# Power_CH341T.net
KiCad netlist of a schematic drawn in Altium Designer
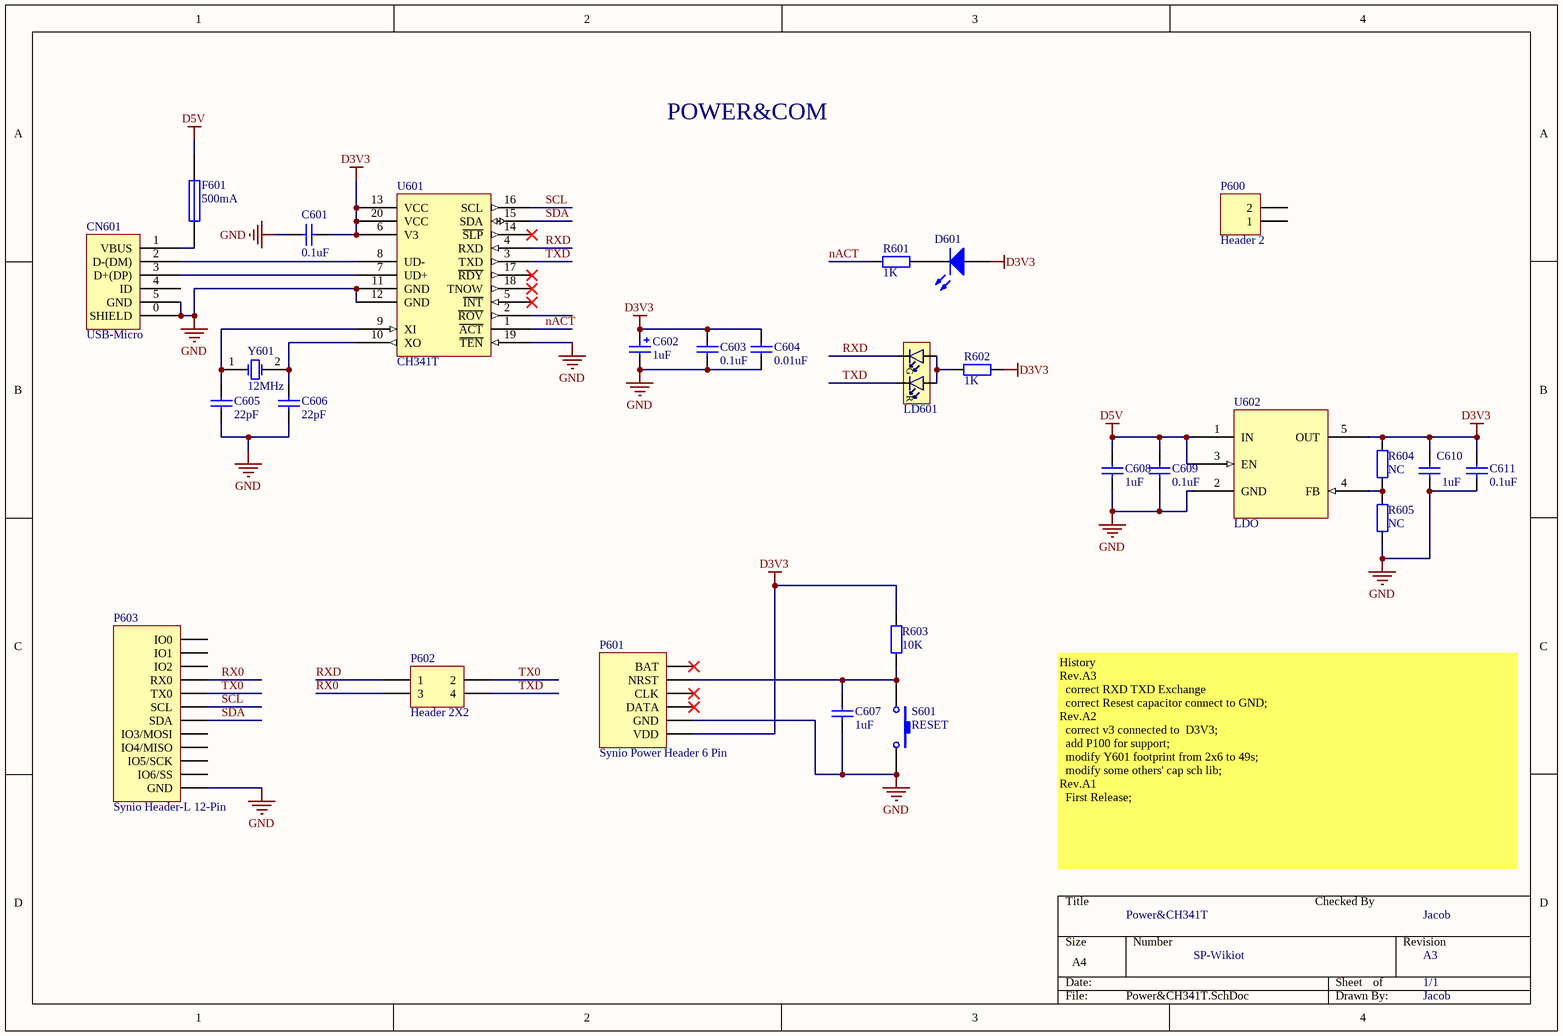
[diagram p0: Power&CH341T.SchDoc]

(export (version "E")
  (design (tool "Eeschema 10.0.6"))
  (components
    (comp (ref "C601")
      (value "0.1uF")
      (footprint "C0603L")
      (description "Capacitor")
      (libsource (lib "Studio") (part "Cap"))
    )
    (comp (ref "C602")
      (value "1uF")
      (footprint "0805M")
      (description "Polarized Capacitor (Radial)")
      (fields (field (name "PUBLISHER") "Altium Limited"))
      (libsource (lib "Studio") (part "Cap Pol1"))
    )
    (comp (ref "C603")
      (value "0.1uF")
      (footprint "C0603L")
      (description "Capacitor")
      (fields (field (name "Comment") "Cap") (field (name "PUBLISHER") "Altium Limited"))
      (libsource (lib "Miscellaneous Devices") (part "Cap"))
    )
    (comp (ref "C604")
      (value "0.01uF")
      (footprint "C0603L")
      (description "Capacitor")
      (fields (field (name "Comment") "Cap") (field (name "PUBLISHER") "Altium Limited"))
      (libsource (lib "Miscellaneous Devices") (part "Cap"))
    )
    (comp (ref "C605")
      (value "22pF")
      (footprint "C0603L")
      (description "Capacitor")
      (fields (field (name "Comment") "Cap") (field (name "PUBLISHER") "Altium Limited"))
      (libsource (lib "Miscellaneous Devices") (part "Cap"))
    )
    (comp (ref "C606")
      (value "22pF")
      (footprint "C0603L")
      (description "Capacitor")
      (fields (field (name "Comment") "Cap") (field (name "PUBLISHER") "Altium Limited"))
      (libsource (lib "Miscellaneous Devices") (part "Cap"))
    )
    (comp (ref "C607")
      (value "1uF")
      (footprint "C0603L")
      (description "Capacitor")
      (fields (field (name "PUBLISHER") "Altium Limited"))
      (libsource (lib "Miscellaneous Devices") (part "Cap"))
    )
    (comp (ref "C608")
      (value "1uF")
      (footprint "C0603L")
      (description "Capacitor")
      (fields (field (name "Comment") "Cap") (field (name "PUBLISHER") "Altium Limited"))
      (libsource (lib "Miscellaneous Devices") (part "Cap"))
    )
    (comp (ref "C609")
      (value "0.1uF")
      (footprint "C0603L")
      (description "Capacitor")
      (fields (field (name "Comment") "Cap") (field (name "PUBLISHER") "Altium Limited"))
      (libsource (lib "Miscellaneous Devices") (part "Cap"))
    )
    (comp (ref "C610")
      (value "1uF")
      (footprint "C0603L")
      (description "Capacitor")
      (fields (field (name "Comment") "Cap") (field (name "PUBLISHER") "Altium Limited"))
      (libsource (lib "Miscellaneous Devices") (part "Cap"))
    )
    (comp (ref "C611")
      (value "0.1uF")
      (footprint "C0603L")
      (description "Capacitor")
      (fields (field (name "Comment") "Cap") (field (name "PUBLISHER") "Altium Limited"))
      (libsource (lib "Miscellaneous Devices") (part "Cap"))
    )
    (comp (ref "CN601")
      (value "USB-Micro")
      (footprint "USB-MICRO-Lite")
      (libsource (lib "Connector") (part "USB-Micro"))
    )
    (comp (ref "D601")
      (value "LED1")
      (footprint "0603pn")
      (description "Typical RED GaAs LED")
      (fields (field (name "PUBLISHER") "Altium Limited"))
      (libsource (lib "Studio") (part "LED1"))
    )
    (comp (ref "F601")
      (value "500mA")
      (footprint "0805")
      (description "Fuse")
      (fields (field (name "PUBLISHER") "Altium Limited"))
      (libsource (lib "Studio") (part "Fuse 1"))
    )
    (comp (ref "LD601")
      (value "LTST-C195KGJRKT")
      (footprint "0805-LED-Bi")
      (description "Avago, HSMF-A203 Bi-Color LED")
      (fields
        (field (name "MANUFACTURER") "Lite-On Inc")
        (field (name "2ND SOURCE PART NUMBER") "859-LTST-C195KGJRKT")
        (field (name "PUBLISHER") "Nordic Semiconductor")
      )
      (libsource (lib "Misc") (part "LED-DUAL"))
    )
    (comp (ref "P600")
      (value "Header 2")
      (footprint "HDR1X2")
      (description "Header, 2-Pin")
      (fields (field (name "PUBLISHER") "Altium Limited"))
      (libsource (lib "Miscellaneous Connectors") (part "Header 2"))
    )
    (comp (ref "P601")
      (value "Synio Power Header 6 Pin")
      (footprint "HDR1X6/2.54MM")
      (libsource (lib "Connector") (part "Synio Power Header 6 Pin"))
    )
    (comp (ref "P602")
      (value "Header 2X2")
      (footprint "HDR2X2/2.54MM")
      (description "Header, 2-Pin, Dual row")
      (fields (field (name "PUBLISHER") "Altium Limited"))
      (libsource (lib "Miscellaneous Connectors") (part "Header 2X2"))
    )
    (comp (ref "P603")
      (value "Synio Header-L 12-Pin")
      (footprint "HDR1X12")
      (description "Synio Header-L, 12-Pin")
      (fields (field (name "PUBLISHER") "Altium Limited"))
      (libsource (lib "Connector") (part "Synio Header-L 12-Pin"))
    )
    (comp (ref "R601")
      (value "1K")
      (footprint "R0603")
      (description "Resistor")
      (fields (field (name "PUBLISHER") "Altium Limited"))
      (libsource (lib "Studio") (part "Res"))
    )
    (comp (ref "R602")
      (value "1K")
      (footprint "0603M")
      (description "Resistor")
      (fields (field (name "PUBLISHER") "Altium Limited"))
      (libsource (lib "") (part "Res2_2"))
    )
    (comp (ref "R603")
      (value "10K")
      (footprint "0603M")
      (description "Resistor")
      (fields (field (name "PUBLISHER") "Altium Limited"))
      (libsource (lib "") (part "Res2_1"))
    )
    (comp (ref "R604")
      (value "NC")
      (footprint "0603M")
      (description "Resistor")
      (fields (field (name "PUBLISHER") "Altium Limited"))
      (libsource (lib "") (part "Res2_1"))
    )
    (comp (ref "R605")
      (value "NC")
      (footprint "0603M")
      (description "Resistor")
      (fields (field (name "PUBLISHER") "Altium Limited"))
      (libsource (lib "Miscellaneous Devices") (part "Res2"))
    )
    (comp (ref "S601")
      (value "RESET")
      (footprint "KEY-2x4-SMD")
      (description "Switch")
      (fields (field (name "PUBLISHER") "Altium Limited"))
      (libsource (lib "Miscellaneous Devices") (part "SW-PB"))
    )
    (comp (ref "U601") (value "CH341T") (footprint "SSOP20") (libsource (lib "Studio") (part "CH341T")))
    (comp (ref "U602")
      (value "LDO")
      (footprint "SOT23-5")
      (description "General LDO SOT23-5")
      (libsource (lib "Power") (part "LDO-SOT23-5"))
    )
    (comp (ref "Y601")
      (value "12MHz")
      (footprint "XTAL_49S")
      (description "Crystal Oscillator")
      (fields (field (name "PUBLISHER") "Altium Limited"))
      (libsource (lib "Miscellaneous Devices") (part "XTAL"))
    )
  )
  (nets
    (net (code "1") (name "/RX0") (class "Default")
      (node (ref "P602") (pin "3") (pinfunction "3_3") (pintype "passive"))
      (node (ref "P603") (pin "9") (pinfunction "RX0_9") (pintype "passive"))
    )
    (net (code "2") (name "/RXD") (class "Default")
      (node (ref "LD601") (pin "1") (pinfunction "C1_1") (pintype "passive"))
      (node (ref "P602") (pin "1") (pinfunction "1_1") (pintype "passive"))
      (node (ref "U601") (pin "4") (pinfunction "RXD_4") (pintype "input"))
    )
    (net (code "3") (name "/SCL") (class "Default")
      (node (ref "P603") (pin "7") (pinfunction "SCL_7") (pintype "passive"))
      (node (ref "U601") (pin "16") (pinfunction "SCL_16") (pintype "output"))
    )
    (net (code "4") (name "/SDA") (class "Default")
      (node (ref "P603") (pin "6") (pinfunction "SDA_6") (pintype "passive"))
      (node (ref "U601") (pin "15") (pinfunction "SDA_15") (pintype "bidirectional"))
    )
    (net (code "5") (name "/TX0") (class "Default")
      (node (ref "P602") (pin "2") (pinfunction "2_2") (pintype "passive"))
      (node (ref "P603") (pin "8") (pinfunction "TX0_8") (pintype "passive"))
    )
    (net (code "6") (name "/TXD") (class "Default")
      (node (ref "LD601") (pin "2") (pinfunction "C2_2") (pintype "passive"))
      (node (ref "P602") (pin "4") (pinfunction "4_4") (pintype "passive"))
      (node (ref "U601") (pin "3") (pinfunction "TXD_3") (pintype "output"))
    )
    (net (code "7") (name "/nACT") (class "Default")
      (node (ref "R601") (pin "1") (pinfunction "1_1") (pintype "passive"))
      (node (ref "U601") (pin "1") (pinfunction "~{ACT}_1") (pintype "power_in"))
    )
    (net (code "8") (name "D3V3") (class "Default")
      (node (ref "C601") (pin "2") (pinfunction "2_2") (pintype "passive"))
      (node (ref "C602") (pin "1") (pinfunction "1_1") (pintype "passive"))
      (node (ref "C603") (pin "2") (pinfunction "2_2") (pintype "passive"))
      (node (ref "C604") (pin "2") (pinfunction "2_2") (pintype "passive"))
      (node (ref "C610") (pin "2") (pinfunction "2_2") (pintype "passive"))
      (node (ref "C611") (pin "2") (pinfunction "2_2") (pintype "passive"))
      (node (ref "D601") (pin "1") (pinfunction "A_1") (pintype "passive"))
      (node (ref "P601") (pin "1") (pinfunction "VDD_1") (pintype "passive"))
      (node (ref "R602") (pin "1") (pinfunction "1_1") (pintype "passive"))
      (node (ref "R603") (pin "1") (pinfunction "1_1") (pintype "passive"))
      (node (ref "R604") (pin "1") (pinfunction "1_1") (pintype "passive"))
      (node (ref "U601") (pin "13") (pinfunction "VCC_13") (pintype "passive"))
      (node (ref "U601") (pin "20") (pinfunction "VCC_20") (pintype "passive"))
      (node (ref "U601") (pin "6") (pinfunction "V3_6") (pintype "power_in"))
      (node (ref "U602") (pin "5") (pinfunction "OUT_5") (pintype "power_in"))
    )
    (net (code "9") (name "D5V") (class "Default")
      (node (ref "C608") (pin "2") (pinfunction "2_2") (pintype "passive"))
      (node (ref "C609") (pin "2") (pinfunction "2_2") (pintype "passive"))
      (node (ref "F601") (pin "1") (pinfunction "1_1") (pintype "passive"))
      (node (ref "U602") (pin "1") (pinfunction "IN_1") (pintype "power_in"))
      (node (ref "U602") (pin "3") (pinfunction "EN_3") (pintype "input"))
    )
    (net (code "10") (name "GND") (class "Default")
      (node (ref "C601") (pin "1") (pinfunction "1_1") (pintype "passive"))
      (node (ref "C602") (pin "2") (pinfunction "2_2") (pintype "passive"))
      (node (ref "C603") (pin "1") (pinfunction "1_1") (pintype "passive"))
      (node (ref "C604") (pin "1") (pinfunction "1_1") (pintype "passive"))
      (node (ref "C605") (pin "1") (pinfunction "1_1") (pintype "passive"))
      (node (ref "C606") (pin "1") (pinfunction "1_1") (pintype "passive"))
      (node (ref "C607") (pin "1") (pinfunction "1_1") (pintype "passive"))
      (node (ref "C608") (pin "1") (pinfunction "1_1") (pintype "passive"))
      (node (ref "C609") (pin "1") (pinfunction "1_1") (pintype "passive"))
      (node (ref "C610") (pin "1") (pinfunction "1_1") (pintype "passive"))
      (node (ref "C611") (pin "1") (pinfunction "1_1") (pintype "passive"))
      (node (ref "CN601") (pin "0") (pinfunction "SHIELD_0") (pintype "passive"))
      (node (ref "CN601") (pin "5") (pinfunction "GND_5") (pintype "passive"))
      (node (ref "P601") (pin "2") (pinfunction "GND_2") (pintype "passive"))
      (node (ref "P603") (pin "1") (pinfunction "GND_1") (pintype "passive"))
      (node (ref "R605") (pin "1") (pinfunction "1_1") (pintype "passive"))
      (node (ref "S601") (pin "1") (pinfunction "1_1") (pintype "passive"))
      (node (ref "U601") (pin "11") (pinfunction "GND_11") (pintype "power_in"))
      (node (ref "U601") (pin "12") (pinfunction "GND_12") (pintype "power_in"))
      (node (ref "U601") (pin "19") (pinfunction "~{TEN}_19") (pintype "input"))
      (node (ref "U602") (pin "2") (pinfunction "GND_2") (pintype "power_in"))
    )
    (net (code "11") (name "Net-(CN601-D+(DP))") (class "Default")
      (node (ref "CN601") (pin "3") (pinfunction "D+(DP)_3") (pintype "passive"))
      (node (ref "U601") (pin "7") (pinfunction "UD+_7") (pintype "passive"))
    )
    (net (code "12") (name "Net-(CN601-D-(DM))") (class "Default")
      (node (ref "CN601") (pin "2") (pinfunction "D-(DM)_2") (pintype "passive"))
      (node (ref "U601") (pin "8") (pinfunction "UD-_8") (pintype "passive"))
    )
    (net (code "13") (name "Net-(CN601-VBUS)") (class "Default")
      (node (ref "CN601") (pin "1") (pinfunction "VBUS_1") (pintype "passive"))
      (node (ref "F601") (pin "2") (pinfunction "2_2") (pintype "passive"))
    )
    (net (code "14") (name "Net-(D601-K)") (class "Default")
      (node (ref "D601") (pin "2") (pinfunction "K_2") (pintype "passive"))
      (node (ref "R601") (pin "2") (pinfunction "2_2") (pintype "passive"))
    )
    (net (code "15") (name "Net-(LD601-A1)") (class "Default")
      (node (ref "LD601") (pin "3") (pinfunction "A2_3") (pintype "passive"))
      (node (ref "LD601") (pin "4") (pinfunction "A1_4") (pintype "passive"))
      (node (ref "R602") (pin "2") (pinfunction "2_2") (pintype "passive"))
    )
    (net (code "16") (name "Net-(P601-NRST)") (class "Default")
      (node (ref "C607") (pin "2") (pinfunction "2_2") (pintype "passive"))
      (node (ref "P601") (pin "5") (pinfunction "NRST_5") (pintype "passive"))
      (node (ref "R603") (pin "2") (pinfunction "2_2") (pintype "passive"))
      (node (ref "S601") (pin "2") (pinfunction "2_2") (pintype "passive"))
    )
    (net (code "17") (name "Net-(U601-XI)") (class "Default")
      (node (ref "C605") (pin "2") (pinfunction "2_2") (pintype "passive"))
      (node (ref "U601") (pin "9") (pinfunction "XI_9") (pintype "input"))
      (node (ref "Y601") (pin "1") (pinfunction "OSC1_1") (pintype "passive"))
    )
    (net (code "18") (name "Net-(U601-XO)") (class "Default")
      (node (ref "C606") (pin "2") (pinfunction "2_2") (pintype "passive"))
      (node (ref "U601") (pin "10") (pinfunction "XO_10") (pintype "output"))
      (node (ref "Y601") (pin "2") (pinfunction "OSC2_2") (pintype "passive"))
    )
    (net (code "19") (name "Net-(U602-FB)") (class "Default")
      (node (ref "R604") (pin "2") (pinfunction "2_2") (pintype "passive"))
      (node (ref "R605") (pin "2") (pinfunction "2_2") (pintype "passive"))
      (node (ref "U602") (pin "4") (pinfunction "FB_4") (pintype "input"))
    )
    (net (code "20") (name "unconnected-(CN601-ID-Pad4)") (class "Default")
      (node (ref "CN601") (pin "4") (pinfunction "ID_4") (pintype "passive"))
    )
    (net (code "21") (name "unconnected-(P600-Pad1)") (class "Default")
      (node (ref "P600") (pin "1") (pinfunction "1_1") (pintype "passive"))
    )
    (net (code "22") (name "unconnected-(P600-Pad2)") (class "Default")
      (node (ref "P600") (pin "2") (pinfunction "2_2") (pintype "passive"))
    )
    (net (code "23") (name "unconnected-(P601-BAT-Pad6)") (class "Default")
      (node (ref "P601") (pin "6") (pinfunction "BAT_6") (pintype "passive+no_connect"))
    )
    (net (code "24") (name "unconnected-(P601-CLK-Pad4)") (class "Default")
      (node (ref "P601") (pin "4") (pinfunction "CLK_4") (pintype "passive+no_connect"))
    )
    (net (code "25") (name "unconnected-(P601-DATA-Pad3)") (class "Default")
      (node (ref "P601") (pin "3") (pinfunction "DATA_3") (pintype "passive+no_connect"))
    )
    (net (code "26") (name "unconnected-(P603-IO0-Pad12)") (class "Default")
      (node (ref "P603") (pin "12") (pinfunction "IO0_12") (pintype "passive"))
    )
    (net (code "27") (name "unconnected-(P603-IO1-Pad11)") (class "Default")
      (node (ref "P603") (pin "11") (pinfunction "IO1_11") (pintype "passive"))
    )
    (net (code "28") (name "unconnected-(P603-IO2-Pad10)") (class "Default")
      (node (ref "P603") (pin "10") (pinfunction "IO2_10") (pintype "passive"))
    )
    (net (code "29") (name "unconnected-(P603-IO3{slash}MOSI-Pad5)") (class "Default")
      (node (ref "P603") (pin "5") (pinfunction "IO3/MOSI_5") (pintype "passive"))
    )
    (net (code "30") (name "unconnected-(P603-IO4{slash}MISO-Pad4)") (class "Default")
      (node (ref "P603") (pin "4") (pinfunction "IO4/MISO_4") (pintype "passive"))
    )
    (net (code "31") (name "unconnected-(P603-IO5{slash}SCK-Pad3)") (class "Default")
      (node (ref "P603") (pin "3") (pinfunction "IO5/SCK_3") (pintype "passive"))
    )
    (net (code "32") (name "unconnected-(P603-IO6{slash}SS-Pad2)") (class "Default")
      (node (ref "P603") (pin "2") (pinfunction "IO6/SS_2") (pintype "passive"))
    )
    (net (code "33") (name "unconnected-(U601-TNOW-Pad18)") (class "Default")
      (node (ref "U601") (pin "18") (pinfunction "TNOW_18") (pintype "output+no_connect"))
    )
    (net (code "34") (name "unconnected-(U601-~{INT}-Pad5)") (class "Default")
      (node (ref "U601") (pin "5") (pinfunction "~{INT}_5") (pintype "input+no_connect"))
    )
    (net (code "35") (name "unconnected-(U601-~{RDY}-Pad17)") (class "Default")
      (node (ref "U601") (pin "17") (pinfunction "~{RDY}_17") (pintype "output+no_connect"))
    )
    (net (code "36") (name "unconnected-(U601-~{ROV}-Pad2)") (class "Default")
      (node (ref "U601") (pin "2") (pinfunction "~{ROV}_2") (pintype "output"))
    )
    (net (code "37") (name "unconnected-(U601-~{SLP}-Pad14)") (class "Default")
      (node (ref "U601") (pin "14") (pinfunction "~{SLP}_14") (pintype "output+no_connect"))
    )
  )
)
